# PSU5V8A.net
KiCad netlist of a schematic drawn in Altium Designer
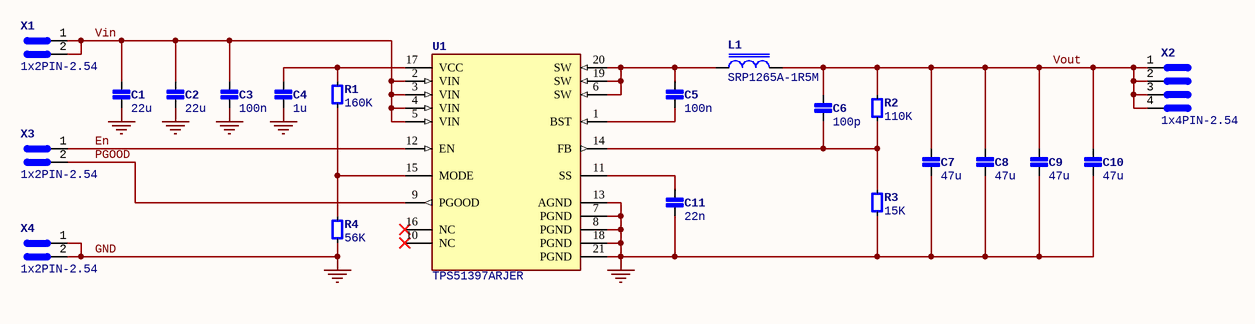
[diagram p0: PSU5V8A.SchDoc]

(export (version "E")
  (design (tool "Eeschema 10.0.6"))
  (components
    (comp (ref "C1") (value "22u") (footprint "CAPC1206N") (libsource (lib "User_leo") (part "CAPACITOR(S)")))
    (comp (ref "C2") (value "22u") (footprint "CAPC1206N") (libsource (lib "User_leo") (part "CAPACITOR(S)")))
    (comp (ref "C3")
      (value "100n")
      (footprint "CAPC0603N")
      (libsource (lib "User_leo") (part "CAPACITOR(S)"))
    )
    (comp (ref "C4") (value "1u") (footprint "CAPC0603N") (libsource (lib "User_leo") (part "CAPACITOR(S)")))
    (comp (ref "C5")
      (value "100n")
      (footprint "CAPC0603N")
      (libsource (lib "User_leo") (part "CAPACITOR(S)"))
    )
    (comp (ref "C6")
      (value "100p")
      (footprint "CAPC0603N")
      (libsource (lib "User_leo") (part "CAPACITOR(S)"))
    )
    (comp (ref "C7") (value "47u") (footprint "CAPC1206N") (libsource (lib "User_leo") (part "CAPACITOR(S)")))
    (comp (ref "C8") (value "47u") (footprint "CAPC1206N") (libsource (lib "User_leo") (part "CAPACITOR(S)")))
    (comp (ref "C9") (value "47u") (footprint "CAPC1206N") (libsource (lib "User_leo") (part "CAPACITOR(S)")))
    (comp (ref "C10")
      (value "47u")
      (footprint "CAPC1206N")
      (libsource (lib "User_leo") (part "CAPACITOR(S)"))
    )
    (comp (ref "C11")
      (value "22n")
      (footprint "CAPC0603N")
      (libsource (lib "User_leo") (part "CAPACITOR(S)"))
    )
    (comp (ref "L1") (value "SRP1265A-1R5M") (footprint "AXIAL0.4") (libsource (lib "User_leo") (part "IND")))
    (comp (ref "R1")
      (value "160K")
      (footprint "RESC0603N")
      (description "电阻")
      (libsource (lib "User_leo") (part "RESISTOR(S)"))
    )
    (comp (ref "R2")
      (value "110K")
      (footprint "RESC0603N")
      (description "电阻")
      (libsource (lib "User_leo") (part "RESISTOR(S)"))
    )
    (comp (ref "R3")
      (value "15K")
      (footprint "RESC0603N")
      (description "电阻")
      (libsource (lib "User_leo") (part "RESISTOR(S)"))
    )
    (comp (ref "R4")
      (value "56K")
      (footprint "RESC0603N")
      (description "电阻")
      (libsource (lib "User_leo") (part "RESISTOR(S)"))
    )
    (comp (ref "U1")
      (value "TPS51397ARJER")
      (footprint "FP-RJE0020B-MFG")
      (description "10-A SYNCHRONOUS STEP-DOWN REGUL")
      (libsource (lib "Altium Content Vault") (part "ab47a50a5143bf718f7c4e945efebe0"))
    )
    (comp (ref "X1")
      (value "1x2PIN-2.54")
      (footprint "HDR1X2-P2.54")
      (description "线路板接插件")
      (libsource (lib "User_leo") (part "2PIN-PCB-Connector"))
    )
    (comp (ref "X2")
      (value "1x4PIN-2.54")
      (footprint "HDR1X4-P2.54")
      (description "线路板接插件")
      (libsource (lib "User_leo") (part "4PIN-PCB-Connector"))
    )
    (comp (ref "X3")
      (value "1x2PIN-2.54")
      (footprint "HDR1X2-P2.54")
      (description "线路板接插件")
      (libsource (lib "User_leo") (part "2PIN-PCB-Connector"))
    )
    (comp (ref "X4")
      (value "1x2PIN-2.54")
      (footprint "HDR1X2-P2.54")
      (description "线路板接插件")
      (libsource (lib "User_leo") (part "2PIN-PCB-Connector"))
    )
  )
  (nets
    (net (code "1") (name "/En") (class "Default")
      (node (ref "U1") (pin "12") (pinfunction "EN_12") (pintype "input"))
      (node (ref "X3") (pin "1") (pinfunction "1_1") (pintype "passive"))
    )
    (net (code "2") (name "/PGOOD") (class "Default")
      (node (ref "U1") (pin "9") (pinfunction "PGOOD_9") (pintype "output"))
      (node (ref "X3") (pin "2") (pinfunction "2_2") (pintype "passive"))
    )
    (net (code "3") (name "/Vin") (class "Default")
      (node (ref "C1") (pin "1") (pinfunction "1_1") (pintype "passive"))
      (node (ref "C2") (pin "1") (pinfunction "1_1") (pintype "passive"))
      (node (ref "C3") (pin "1") (pinfunction "1_1") (pintype "passive"))
      (node (ref "U1") (pin "2") (pinfunction "VIN_2") (pintype "input"))
      (node (ref "U1") (pin "3") (pinfunction "VIN_3") (pintype "input"))
      (node (ref "U1") (pin "4") (pinfunction "VIN_4") (pintype "input"))
      (node (ref "U1") (pin "5") (pinfunction "VIN_5") (pintype "input"))
      (node (ref "X1") (pin "1") (pinfunction "1_1") (pintype "passive"))
      (node (ref "X1") (pin "2") (pinfunction "2_2") (pintype "passive"))
    )
    (net (code "4") (name "/Vout") (class "Default")
      (node (ref "C10") (pin "1") (pinfunction "1_1") (pintype "passive"))
      (node (ref "C6") (pin "1") (pinfunction "1_1") (pintype "passive"))
      (node (ref "C7") (pin "1") (pinfunction "1_1") (pintype "passive"))
      (node (ref "C8") (pin "1") (pinfunction "1_1") (pintype "passive"))
      (node (ref "C9") (pin "1") (pinfunction "1_1") (pintype "passive"))
      (node (ref "L1") (pin "2") (pinfunction "2_2") (pintype "passive"))
      (node (ref "R2") (pin "1") (pinfunction "1_1") (pintype "passive"))
      (node (ref "X2") (pin "1") (pinfunction "1_1") (pintype "passive"))
      (node (ref "X2") (pin "2") (pinfunction "2_2") (pintype "passive"))
      (node (ref "X2") (pin "3") (pinfunction "3_3") (pintype "passive"))
      (node (ref "X2") (pin "4") (pinfunction "4_4") (pintype "passive"))
    )
    (net (code "5") (name "GND") (class "Default")
      (node (ref "C1") (pin "2") (pinfunction "2_2") (pintype "passive"))
      (node (ref "C10") (pin "2") (pinfunction "2_2") (pintype "passive"))
      (node (ref "C11") (pin "2") (pinfunction "2_2") (pintype "passive"))
      (node (ref "C2") (pin "2") (pinfunction "2_2") (pintype "passive"))
      (node (ref "C3") (pin "2") (pinfunction "2_2") (pintype "passive"))
      (node (ref "C4") (pin "2") (pinfunction "2_2") (pintype "passive"))
      (node (ref "C7") (pin "2") (pinfunction "2_2") (pintype "passive"))
      (node (ref "C8") (pin "2") (pinfunction "2_2") (pintype "passive"))
      (node (ref "C9") (pin "2") (pinfunction "2_2") (pintype "passive"))
      (node (ref "R3") (pin "2") (pinfunction "2_2") (pintype "passive"))
      (node (ref "R4") (pin "1") (pinfunction "1_1") (pintype "passive"))
      (node (ref "U1") (pin "13") (pinfunction "AGND_13") (pintype "power_in"))
      (node (ref "U1") (pin "18") (pinfunction "PGND_18") (pintype "power_in"))
      (node (ref "U1") (pin "21") (pinfunction "PGND_21") (pintype "power_in"))
      (node (ref "U1") (pin "7") (pinfunction "PGND_7") (pintype "power_in"))
      (node (ref "U1") (pin "8") (pinfunction "PGND_8") (pintype "power_in"))
      (node (ref "X4") (pin "1") (pinfunction "1_1") (pintype "passive"))
      (node (ref "X4") (pin "2") (pinfunction "2_2") (pintype "passive"))
    )
    (net (code "6") (name "Net-(C5-Pad1)") (class "Default")
      (node (ref "C5") (pin "1") (pinfunction "1_1") (pintype "passive"))
      (node (ref "L1") (pin "1") (pinfunction "1_1") (pintype "passive"))
      (node (ref "U1") (pin "19") (pinfunction "SW_19") (pintype "input"))
      (node (ref "U1") (pin "20") (pinfunction "SW_20") (pintype "input"))
      (node (ref "U1") (pin "6") (pinfunction "SW_6") (pintype "input"))
    )
    (net (code "7") (name "Net-(U1-BST)") (class "Default")
      (node (ref "C5") (pin "2") (pinfunction "2_2") (pintype "passive"))
      (node (ref "U1") (pin "1") (pinfunction "BST_1") (pintype "input"))
    )
    (net (code "8") (name "Net-(U1-FB)") (class "Default")
      (node (ref "C6") (pin "2") (pinfunction "2_2") (pintype "passive"))
      (node (ref "R2") (pin "2") (pinfunction "2_2") (pintype "passive"))
      (node (ref "R3") (pin "1") (pinfunction "1_1") (pintype "passive"))
      (node (ref "U1") (pin "14") (pinfunction "FB_14") (pintype "output"))
    )
    (net (code "9") (name "Net-(U1-MODE)") (class "Default")
      (node (ref "R1") (pin "1") (pinfunction "1_1") (pintype "passive"))
      (node (ref "R4") (pin "2") (pinfunction "2_2") (pintype "passive"))
      (node (ref "U1") (pin "15") (pinfunction "MODE_15") (pintype "passive"))
    )
    (net (code "10") (name "Net-(U1-SS)") (class "Default")
      (node (ref "C11") (pin "1") (pinfunction "1_1") (pintype "passive"))
      (node (ref "U1") (pin "11") (pinfunction "SS_11") (pintype "passive"))
    )
    (net (code "11") (name "Net-(U1-VCC)") (class "Default")
      (node (ref "C4") (pin "1") (pinfunction "1_1") (pintype "passive"))
      (node (ref "R1") (pin "2") (pinfunction "2_2") (pintype "passive"))
      (node (ref "U1") (pin "17") (pinfunction "VCC_17") (pintype "power_in"))
    )
    (net (code "12") (name "unconnected-(U1-NC-Pad10)") (class "Default")
      (node (ref "U1") (pin "10") (pinfunction "NC_10") (pintype "passive+no_connect"))
    )
    (net (code "13") (name "unconnected-(U1-NC-Pad16)") (class "Default")
      (node (ref "U1") (pin "16") (pinfunction "NC_16") (pintype "passive+no_connect"))
    )
  )
)
